# kitchenClock_v2.net
KiCad netlist of a schematic drawn in EAGLE
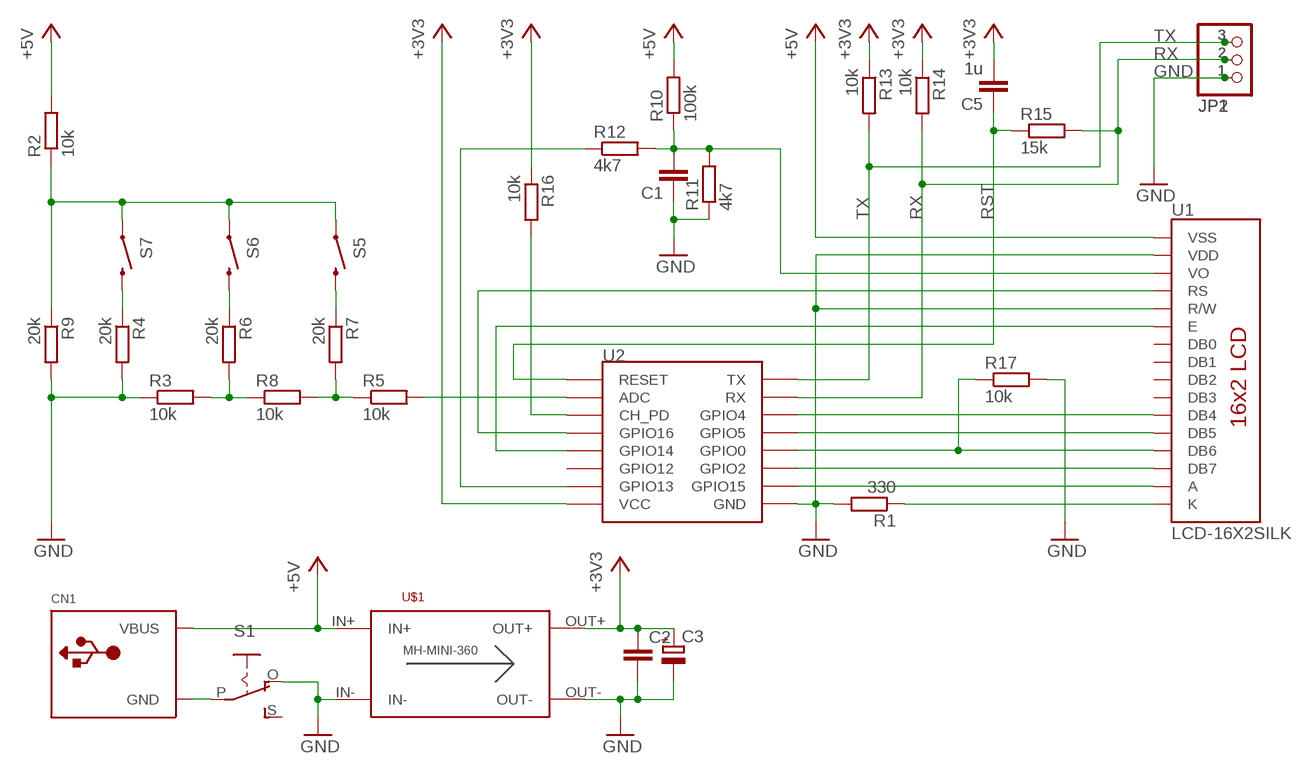
[diagram p0: schematic, sheet 1]

(export (version "E")
  (design (tool "Eeschema 10.0.6"))
  (components
    (comp (ref "C1")
      (value "C-EU050-025X075")
      (footprint "eagle-import:C050-025X075")
      (libsource (lib "eagle-import") (part "C-EU050-025X075"))
    )
    (comp (ref "C2")
      (value "C-EU025-025X050")
      (footprint "eagle-import:C025-025X050")
      (libsource (lib "eagle-import") (part "C-EU025-025X050"))
    )
    (comp (ref "C3")
      (value "CPOL-EUTT2D5L")
      (footprint "eagle-import:TT2D5L")
      (libsource (lib "eagle-import") (part "CPOL-EUTT2D5L"))
    )
    (comp (ref "C5")
      (value "1u")
      (footprint "eagle-import:C025-025X050")
      (libsource (lib "eagle-import") (part "C-EU025-025X050"))
    )
    (comp (ref "CN1")
      (value "USBPWR-ONLY")
      (footprint "eagle-import:USB-MINIB-THM")
      (libsource (lib "eagle-import") (part "USBPWR-ONLY"))
    )
    (comp (ref "JP1")
      (value "PINHD-1X3/90")
      (footprint "eagle-import:1X03_90")
      (libsource (lib "eagle-import") (part "PINHD-1X3/90"))
    )
    (comp (ref "JP2")
      (value "PINHD-1X3")
      (footprint "eagle-import:1X03")
      (libsource (lib "eagle-import") (part "PINHD-1X3"))
    )
    (comp (ref "R1")
      (value "330")
      (footprint "eagle-import:0204_7")
      (libsource (lib "eagle-import") (part "R-EU_0204/7"))
    )
    (comp (ref "R2")
      (value "10k")
      (footprint "eagle-import:0204_7")
      (libsource (lib "eagle-import") (part "R-EU_0204/7"))
    )
    (comp (ref "R3")
      (value "10k")
      (footprint "eagle-import:0204_7")
      (libsource (lib "eagle-import") (part "R-EU_0204/7"))
    )
    (comp (ref "R4")
      (value "20k")
      (footprint "eagle-import:0204_7")
      (libsource (lib "eagle-import") (part "R-EU_0204/7"))
    )
    (comp (ref "R5")
      (value "10k")
      (footprint "eagle-import:0204_7")
      (libsource (lib "eagle-import") (part "R-EU_0204/7"))
    )
    (comp (ref "R6")
      (value "20k")
      (footprint "eagle-import:0204_7")
      (libsource (lib "eagle-import") (part "R-EU_0204/7"))
    )
    (comp (ref "R7")
      (value "20k")
      (footprint "eagle-import:0204_7")
      (libsource (lib "eagle-import") (part "R-EU_0204/7"))
    )
    (comp (ref "R8")
      (value "10k")
      (footprint "eagle-import:0204_7")
      (libsource (lib "eagle-import") (part "R-EU_0204/7"))
    )
    (comp (ref "R9")
      (value "20k")
      (footprint "eagle-import:0204_7")
      (libsource (lib "eagle-import") (part "R-EU_0204/7"))
    )
    (comp (ref "R10")
      (value "100k")
      (footprint "eagle-import:0204_7")
      (libsource (lib "eagle-import") (part "R-EU_0204/7"))
    )
    (comp (ref "R11")
      (value "4k7")
      (footprint "eagle-import:0204_7")
      (libsource (lib "eagle-import") (part "R-EU_0204/7"))
    )
    (comp (ref "R12")
      (value "4k7")
      (footprint "eagle-import:0204_7")
      (libsource (lib "eagle-import") (part "R-EU_0204/7"))
    )
    (comp (ref "R13")
      (value "10k")
      (footprint "eagle-import:0204_7")
      (libsource (lib "eagle-import") (part "R-EU_0204/7"))
    )
    (comp (ref "R14")
      (value "10k")
      (footprint "eagle-import:0204_7")
      (libsource (lib "eagle-import") (part "R-EU_0204/7"))
    )
    (comp (ref "R15")
      (value "15k")
      (footprint "eagle-import:0204_7")
      (libsource (lib "eagle-import") (part "R-EU_0204/7"))
    )
    (comp (ref "R16")
      (value "10k")
      (footprint "eagle-import:0204_7")
      (libsource (lib "eagle-import") (part "R-EU_0204/7"))
    )
    (comp (ref "R17")
      (value "10k")
      (footprint "eagle-import:M0805")
      (libsource (lib "eagle-import") (part "R-EU_M0805"))
    )
    (comp (ref "S1")
      (value "EG1218S")
      (footprint "eagle-import:EG1218")
      (libsource (lib "eagle-import") (part "EG1218S"))
    )
    (comp (ref "S5")
      (value "SWITCH-MOMENTARY-2SIDE_EZ")
      (footprint "eagle-import:TACTILE-PTH-SIDEEZ")
      (libsource (lib "eagle-import") (part "SWITCH-MOMENTARY-2SIDE_EZ"))
    )
    (comp (ref "S6")
      (value "SWITCH-MOMENTARY-2SIDE_EZ")
      (footprint "eagle-import:TACTILE-PTH-SIDEEZ")
      (libsource (lib "eagle-import") (part "SWITCH-MOMENTARY-2SIDE_EZ"))
    )
    (comp (ref "S7")
      (value "SWITCH-MOMENTARY-2SIDE_EZ")
      (footprint "eagle-import:TACTILE-PTH-SIDEEZ")
      (libsource (lib "eagle-import") (part "SWITCH-MOMENTARY-2SIDE_EZ"))
    )
    (comp (ref "U$1")
      (value "DC-DC_CONV_MINISTD")
      (footprint "eagle-import:DC-DC_CONV_MINI")
      (libsource (lib "eagle-import") (part "DC-DC_CONV_MINISTD"))
    )
    (comp (ref "U1")
      (value "LCD-16X2SILK")
      (footprint "eagle-import:LCD-16X2")
      (libsource (lib "eagle-import") (part "LCD-16X2SILK"))
    )
    (comp (ref "U2")
      (value "ESP12EDIP")
      (footprint "eagle-import:ESP-12-BREAKOUT")
      (libsource (lib "eagle-import") (part "ESP12EDIP"))
    )
  )
  (nets
    (net (code "1") (name "+3V3") (class "Default")
      (node (ref "C2") (pin "1") (pinfunction "1_1") (pintype "passive"))
      (node (ref "C3") (pin "+") (pinfunction "+_+") (pintype "passive"))
      (node (ref "C5") (pin "2") (pinfunction "2_2") (pintype "passive"))
      (node (ref "R13") (pin "1") (pinfunction "1_1") (pintype "passive"))
      (node (ref "R14") (pin "1") (pinfunction "1_1") (pintype "passive"))
      (node (ref "R16") (pin "1") (pinfunction "1_1") (pintype "passive"))
      (node (ref "U$1") (pin "OUT+") (pinfunction "OUT+_OUT+") (pintype "bidirectional"))
      (node (ref "U2") (pin "P$1") (pinfunction "VCC_P$1") (pintype "bidirectional"))
    )
    (net (code "2") (name "+5V") (class "Default")
      (node (ref "CN1") (pin "VBUS") (pinfunction "VBUS_VBUS") (pintype "power_in"))
      (node (ref "R10") (pin "2") (pinfunction "2_2") (pintype "passive"))
      (node (ref "R2") (pin "2") (pinfunction "2_2") (pintype "passive"))
      (node (ref "U$1") (pin "IN+") (pinfunction "IN+_IN+") (pintype "bidirectional"))
      (node (ref "U1") (pin "1") (pinfunction "VSS_1") (pintype "power_in"))
    )
    (net (code "3") (name "/RST") (class "Default")
      (node (ref "C5") (pin "1") (pinfunction "1_1") (pintype "passive"))
      (node (ref "R15") (pin "1") (pinfunction "1_1") (pintype "passive"))
      (node (ref "U2") (pin "P$8") (pinfunction "RESET_P$8") (pintype "bidirectional"))
    )
    (net (code "4") (name "/RX") (class "Default")
      (node (ref "JP1") (pin "2") (pinfunction "2_2") (pintype "passive"))
      (node (ref "JP2") (pin "2") (pinfunction "2_2") (pintype "passive"))
      (node (ref "R14") (pin "2") (pinfunction "2_2") (pintype "passive"))
      (node (ref "R15") (pin "2") (pinfunction "2_2") (pintype "passive"))
      (node (ref "U2") (pin "P$15") (pinfunction "RX_P$15") (pintype "bidirectional"))
    )
    (net (code "5") (name "/TX") (class "Default")
      (node (ref "JP1") (pin "3") (pinfunction "3_3") (pintype "passive"))
      (node (ref "JP2") (pin "3") (pinfunction "3_3") (pintype "passive"))
      (node (ref "R13") (pin "2") (pinfunction "2_2") (pintype "passive"))
      (node (ref "U2") (pin "P$16") (pinfunction "TX_P$16") (pintype "bidirectional"))
    )
    (net (code "6") (name "GND") (class "Default")
      (node (ref "C1") (pin "1") (pinfunction "1_1") (pintype "passive"))
      (node (ref "C2") (pin "2") (pinfunction "2_2") (pintype "passive"))
      (node (ref "C3") (pin "-") (pinfunction "-_-") (pintype "passive"))
      (node (ref "JP1") (pin "1") (pinfunction "1_1") (pintype "passive"))
      (node (ref "JP2") (pin "1") (pinfunction "1_1") (pintype "passive"))
      (node (ref "R1") (pin "2") (pinfunction "2_2") (pintype "passive"))
      (node (ref "R11") (pin "1") (pinfunction "1_1") (pintype "passive"))
      (node (ref "R17") (pin "2") (pinfunction "2_2") (pintype "passive"))
      (node (ref "R3") (pin "1") (pinfunction "1_1") (pintype "passive"))
      (node (ref "R4") (pin "2") (pinfunction "2_2") (pintype "passive"))
      (node (ref "R9") (pin "2") (pinfunction "2_2") (pintype "passive"))
      (node (ref "S1") (pin "O") (pinfunction "O_O") (pintype "passive"))
      (node (ref "U$1") (pin "IN-") (pinfunction "IN-_IN-") (pintype "bidirectional"))
      (node (ref "U$1") (pin "OUT-") (pinfunction "OUT-_OUT-") (pintype "bidirectional"))
      (node (ref "U1") (pin "2") (pinfunction "VDD_2") (pintype "power_in"))
      (node (ref "U1") (pin "5") (pinfunction "R/W_5") (pintype "input"))
      (node (ref "U2") (pin "P$9") (pinfunction "GND_P$9") (pintype "bidirectional"))
    )
    (net (code "7") (name "Net-(CN1-GND-PadGND1)") (class "Default")
      (node (ref "CN1") (pin "GND") (pinfunction "GND_GND") (pintype "power_in"))
      (node (ref "CN1") (pin "GND1") (pinfunction "GND_GND1") (pintype "power_in"))
      (node (ref "CN1") (pin "GND2") (pinfunction "GND_GND2") (pintype "power_in"))
      (node (ref "CN1") (pin "GND3") (pinfunction "GND_GND3") (pintype "power_in"))
      (node (ref "CN1") (pin "GND4") (pinfunction "GND_GND4") (pintype "power_in"))
      (node (ref "S1") (pin "P") (pinfunction "P_P") (pintype "passive"))
    )
    (net (code "8") (name "Net-(R2-Pad1)") (class "Default")
      (node (ref "R2") (pin "1") (pinfunction "1_1") (pintype "passive"))
      (node (ref "R9") (pin "1") (pinfunction "1_1") (pintype "passive"))
      (node (ref "S5") (pin "1") (pinfunction "1_1") (pintype "passive"))
      (node (ref "S6") (pin "1") (pinfunction "1_1") (pintype "passive"))
      (node (ref "S7") (pin "1") (pinfunction "1_1") (pintype "passive"))
    )
    (net (code "9") (name "Net-(R3-Pad2)") (class "Default")
      (node (ref "R3") (pin "2") (pinfunction "2_2") (pintype "passive"))
      (node (ref "R6") (pin "2") (pinfunction "2_2") (pintype "passive"))
      (node (ref "R8") (pin "1") (pinfunction "1_1") (pintype "passive"))
    )
    (net (code "10") (name "Net-(R4-Pad1)") (class "Default")
      (node (ref "R4") (pin "1") (pinfunction "1_1") (pintype "passive"))
      (node (ref "S7") (pin "2") (pinfunction "2_2") (pintype "passive"))
    )
    (net (code "11") (name "Net-(R5-Pad1)") (class "Default")
      (node (ref "R5") (pin "1") (pinfunction "1_1") (pintype "passive"))
      (node (ref "R7") (pin "2") (pinfunction "2_2") (pintype "passive"))
      (node (ref "R8") (pin "2") (pinfunction "2_2") (pintype "passive"))
    )
    (net (code "12") (name "Net-(R6-Pad1)") (class "Default")
      (node (ref "R6") (pin "1") (pinfunction "1_1") (pintype "passive"))
      (node (ref "S6") (pin "2") (pinfunction "2_2") (pintype "passive"))
    )
    (net (code "13") (name "Net-(R7-Pad1)") (class "Default")
      (node (ref "R7") (pin "1") (pinfunction "1_1") (pintype "passive"))
      (node (ref "S5") (pin "2") (pinfunction "2_2") (pintype "passive"))
    )
    (net (code "14") (name "Net-(U1-A)") (class "Default")
      (node (ref "U1") (pin "15") (pinfunction "A_15") (pintype "power_in"))
      (node (ref "U2") (pin "P$10") (pinfunction "GPIO15_P$10") (pintype "bidirectional"))
    )
    (net (code "15") (name "Net-(U1-DB4)") (class "Default")
      (node (ref "U1") (pin "11") (pinfunction "DB4_11") (pintype "bidirectional"))
      (node (ref "U2") (pin "P$14") (pinfunction "GPIO4_P$14") (pintype "bidirectional"))
    )
    (net (code "16") (name "Net-(U1-DB5)") (class "Default")
      (node (ref "U1") (pin "12") (pinfunction "DB5_12") (pintype "bidirectional"))
      (node (ref "U2") (pin "P$13") (pinfunction "GPIO5_P$13") (pintype "bidirectional"))
    )
    (net (code "17") (name "Net-(U1-DB6)") (class "Default")
      (node (ref "R17") (pin "1") (pinfunction "1_1") (pintype "passive"))
      (node (ref "U1") (pin "13") (pinfunction "DB6_13") (pintype "bidirectional"))
      (node (ref "U2") (pin "P$12") (pinfunction "GPIO0_P$12") (pintype "bidirectional"))
    )
    (net (code "18") (name "Net-(U1-DB7)") (class "Default")
      (node (ref "U1") (pin "14") (pinfunction "DB7_14") (pintype "bidirectional"))
      (node (ref "U2") (pin "P$11") (pinfunction "GPIO2_P$11") (pintype "bidirectional"))
    )
    (net (code "19") (name "Net-(U1-E)") (class "Default")
      (node (ref "U1") (pin "6") (pinfunction "E_6") (pintype "input"))
      (node (ref "U2") (pin "P$4") (pinfunction "GPIO14_P$4") (pintype "bidirectional"))
    )
    (net (code "20") (name "Net-(U1-K)") (class "Default")
      (node (ref "R1") (pin "1") (pinfunction "1_1") (pintype "passive"))
      (node (ref "U1") (pin "16") (pinfunction "K_16") (pintype "power_in"))
    )
    (net (code "21") (name "Net-(U1-RS)") (class "Default")
      (node (ref "U1") (pin "4") (pinfunction "RS_4") (pintype "input"))
      (node (ref "U2") (pin "P$5") (pinfunction "GPIO16_P$5") (pintype "bidirectional"))
    )
    (net (code "22") (name "Net-(U1-VO)") (class "Default")
      (node (ref "C1") (pin "2") (pinfunction "2_2") (pintype "passive"))
      (node (ref "R10") (pin "1") (pinfunction "1_1") (pintype "passive"))
      (node (ref "R11") (pin "2") (pinfunction "2_2") (pintype "passive"))
      (node (ref "R12") (pin "2") (pinfunction "2_2") (pintype "passive"))
      (node (ref "U1") (pin "3") (pinfunction "VO_3") (pintype "bidirectional"))
    )
    (net (code "23") (name "Net-(U2-ADC)") (class "Default")
      (node (ref "R5") (pin "2") (pinfunction "2_2") (pintype "passive"))
      (node (ref "U2") (pin "P$7") (pinfunction "ADC_P$7") (pintype "bidirectional"))
    )
    (net (code "24") (name "Net-(U2-CH_PD)") (class "Default")
      (node (ref "R16") (pin "2") (pinfunction "2_2") (pintype "passive"))
      (node (ref "U2") (pin "P$6") (pinfunction "CH_PD_P$6") (pintype "bidirectional"))
    )
    (net (code "25") (name "Net-(U2-GPIO13)") (class "Default")
      (node (ref "R12") (pin "1") (pinfunction "1_1") (pintype "passive"))
      (node (ref "U2") (pin "P$2") (pinfunction "GPIO13_P$2") (pintype "bidirectional"))
    )
    (net (code "26") (name "unconnected-(S1-PadS)") (class "Default")
      (node (ref "S1") (pin "S") (pinfunction "S_S") (pintype "passive"))
    )
    (net (code "27") (name "unconnected-(U1-DB0-Pad7)") (class "Default")
      (node (ref "U1") (pin "7") (pinfunction "DB0_7") (pintype "bidirectional"))
    )
    (net (code "28") (name "unconnected-(U1-DB1-Pad8)") (class "Default")
      (node (ref "U1") (pin "8") (pinfunction "DB1_8") (pintype "bidirectional"))
    )
    (net (code "29") (name "unconnected-(U1-DB2-Pad9)") (class "Default")
      (node (ref "U1") (pin "9") (pinfunction "DB2_9") (pintype "bidirectional"))
    )
    (net (code "30") (name "unconnected-(U1-DB3-Pad10)") (class "Default")
      (node (ref "U1") (pin "10") (pinfunction "DB3_10") (pintype "bidirectional"))
    )
    (net (code "31") (name "unconnected-(U2-GPIO12-PadP$3)") (class "Default")
      (node (ref "U2") (pin "P$3") (pinfunction "GPIO12_P$3") (pintype "bidirectional"))
    )
  )
)
